# Control_Board.net
KiCad netlist of a schematic drawn in Altium Designer
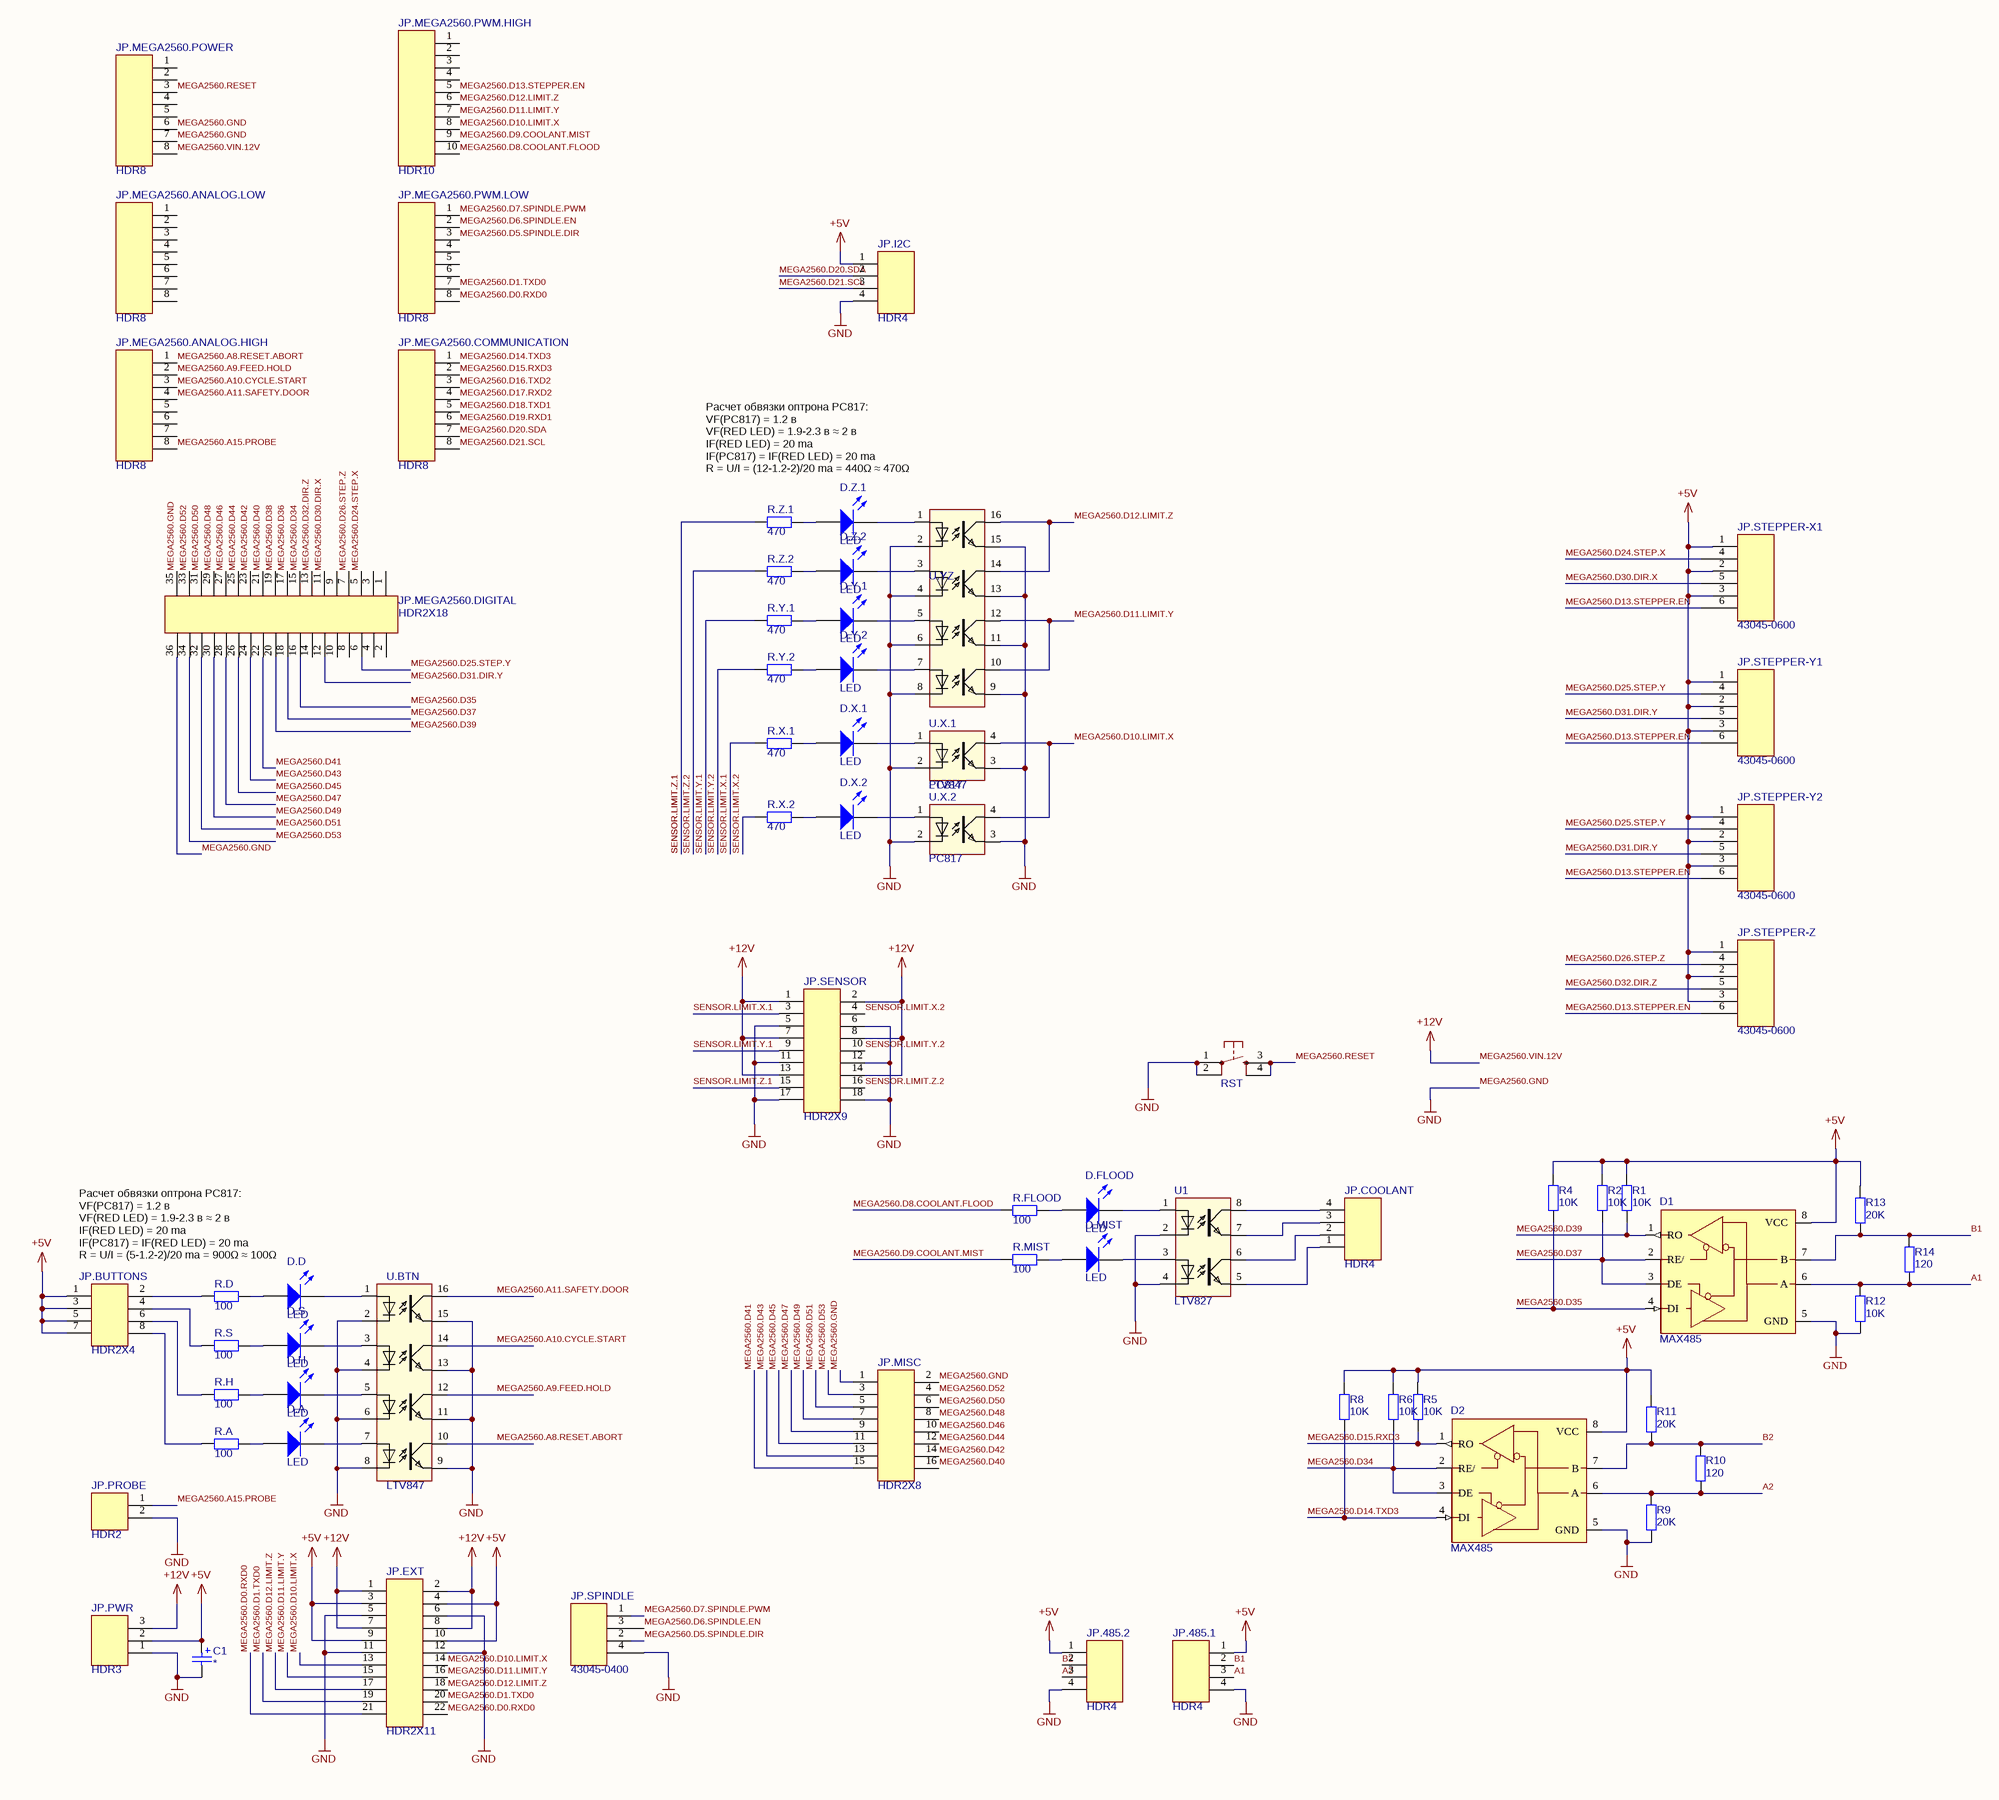
[diagram p0: Control.Board.SchDoc]

(export (version "E")
  (design (tool "Eeschema 10.0.6"))
  (components
    (comp (ref "C1")
      (value "*")
      (footprint "E3,5-8")
      (description "Polarized Capacitor (Radial)")
      (fields (field (name "PUBLISHER") "Altium Limited"))
      (libsource (lib "Net173") (part "CAP.POL"))
    )
    (comp (ref "D.A")
      (value "LED")
      (footprint "1206-SMD-LED")
      (fields (field (name "PUBLISHER") "Altium Limited"))
      (libsource (lib "Net173") (part "LED"))
    )
    (comp (ref "D.D")
      (value "LED")
      (footprint "1206-SMD-LED")
      (fields (field (name "PUBLISHER") "Altium Limited"))
      (libsource (lib "Net173") (part "LED"))
    )
    (comp (ref "D.FLOOD")
      (value "LED")
      (footprint "1206-SMD-LED")
      (fields (field (name "PUBLISHER") "Altium Limited"))
      (libsource (lib "Net173") (part "LED"))
    )
    (comp (ref "D.H")
      (value "LED")
      (footprint "1206-SMD-LED")
      (fields (field (name "PUBLISHER") "Altium Limited"))
      (libsource (lib "Net173") (part "LED"))
    )
    (comp (ref "D.MIST")
      (value "LED")
      (footprint "1206-SMD-LED")
      (fields (field (name "PUBLISHER") "Altium Limited"))
      (libsource (lib "Net173") (part "LED"))
    )
    (comp (ref "D.S")
      (value "LED")
      (footprint "1206-SMD-LED")
      (fields (field (name "PUBLISHER") "Altium Limited"))
      (libsource (lib "Net173") (part "LED"))
    )
    (comp (ref "D.X.1")
      (value "LED")
      (footprint "1206-SMD-LED")
      (fields (field (name "PUBLISHER") "Altium Limited"))
      (libsource (lib "Net173") (part "LED"))
    )
    (comp (ref "D.X.2")
      (value "LED")
      (footprint "1206-SMD-LED")
      (fields (field (name "PUBLISHER") "Altium Limited"))
      (libsource (lib "Net173") (part "LED"))
    )
    (comp (ref "D.Y.1")
      (value "LED")
      (footprint "1206-SMD-LED")
      (fields (field (name "PUBLISHER") "Altium Limited"))
      (libsource (lib "Net173") (part "LED"))
    )
    (comp (ref "D.Y.2")
      (value "LED")
      (footprint "1206-SMD-LED")
      (fields (field (name "PUBLISHER") "Altium Limited"))
      (libsource (lib "Net173") (part "LED"))
    )
    (comp (ref "D.Z.1")
      (value "LED")
      (footprint "1206-SMD-LED")
      (fields (field (name "PUBLISHER") "Altium Limited"))
      (libsource (lib "Net173") (part "LED"))
    )
    (comp (ref "D.Z.2")
      (value "LED")
      (footprint "1206-SMD-LED")
      (fields (field (name "PUBLISHER") "Altium Limited"))
      (libsource (lib "Net173") (part "LED"))
    )
    (comp (ref "D1") (value "MAX485") (footprint "DIP8") (libsource (lib "Net173") (part "MAX485")))
    (comp (ref "D2") (value "MAX485") (footprint "DIP8") (libsource (lib "Net173") (part "MAX485")))
    (comp (ref "JP.485.1") (value "HDR4") (footprint "HDR1X4") (libsource (lib "") (part "HDR4_1")))
    (comp (ref "JP.485.2") (value "HDR4") (footprint "HDR1X4") (libsource (lib "Net173") (part "HDR4")))
    (comp (ref "JP.BUTTONS") (value "HDR2X4") (footprint "HDR2X4") (libsource (lib "Net173") (part "HDR2X4")))
    (comp (ref "JP.COOLANT") (value "HDR4") (footprint "HDR1X4H") (libsource (lib "") (part "HDR4_2")))
    (comp (ref "JP.EXT") (value "HDR2X11") (footprint "HDR2X11") (libsource (lib "Net173") (part "HDR2X11")))
    (comp (ref "JP.I2C") (value "HDR4") (footprint "HDR1X4") (libsource (lib "Net173") (part "HDR4")))
    (comp (ref "JP.MEGA2560.ANALOG.HIGH")
      (value "HDR8")
      (footprint "HDR8-BOTTOM")
      (libsource (lib "Net173") (part "HDR8"))
    )
    (comp (ref "JP.MEGA2560.ANALOG.LOW")
      (value "HDR8")
      (footprint "HDR8-BOTTOM")
      (libsource (lib "Net173") (part "HDR8"))
    )
    (comp (ref "JP.MEGA2560.COMMUNICATION")
      (value "HDR8")
      (footprint "HDR8-BOTTOM")
      (libsource (lib "Net173") (part "HDR8"))
    )
    (comp (ref "JP.MEGA2560.DIGITAL")
      (value "HDR2X18")
      (footprint "HDR2X18-BOTTOM")
      (libsource (lib "Net173") (part "HDR2X18"))
    )
    (comp (ref "JP.MEGA2560.POWER")
      (value "HDR8")
      (footprint "HDR8-BOTTOM")
      (libsource (lib "Net173") (part "HDR8"))
    )
    (comp (ref "JP.MEGA2560.PWM.HIGH")
      (value "HDR10")
      (footprint "HDR10-BOTTOM")
      (libsource (lib "Net173") (part "HDR10"))
    )
    (comp (ref "JP.MEGA2560.PWM.LOW")
      (value "HDR8")
      (footprint "HDR8-BOTTOM")
      (libsource (lib "Net173") (part "HDR8"))
    )
    (comp (ref "JP.MISC") (value "HDR2X8") (footprint "HDR2X8") (libsource (lib "Net173") (part "HDR2X8")))
    (comp (ref "JP.PROBE") (value "HDR2") (footprint "HDR1X2") (libsource (lib "Net173") (part "HDR2")))
    (comp (ref "JP.PWR") (value "HDR3") (footprint "HDR1X3H") (libsource (lib "Net173") (part "HDR3")))
    (comp (ref "JP.SENSOR") (value "HDR2X9") (footprint "HDR2X9") (libsource (lib "Net173") (part "HDR2X9")))
    (comp (ref "JP.SPINDLE")
      (value "43045-0400")
      (footprint "43045-0400")
      (libsource (lib "Net173") (part "43045-0400"))
    )
    (comp (ref "JP.STEPPER-X1")
      (value "43045-0600")
      (footprint "43045-0600")
      (libsource (lib "Net173") (part "43045-0600"))
    )
    (comp (ref "JP.STEPPER-Y1")
      (value "43045-0600")
      (footprint "43045-0600")
      (libsource (lib "Net173") (part "43045-0600"))
    )
    (comp (ref "JP.STEPPER-Y2")
      (value "43045-0600")
      (footprint "43045-0600")
      (libsource (lib "Net173") (part "43045-0600"))
    )
    (comp (ref "JP.STEPPER-Z")
      (value "43045-0600")
      (footprint "43045-0600")
      (libsource (lib "Net173") (part "43045-0600"))
    )
    (comp (ref "R.A") (value "100") (footprint "1206-SMD-RES") (libsource (lib "Net173") (part "RES")))
    (comp (ref "R.D") (value "100") (footprint "1206-SMD-RES") (libsource (lib "Net173") (part "RES")))
    (comp (ref "R.FLOOD") (value "100") (footprint "1206-SMD-RES") (libsource (lib "Net173") (part "RES")))
    (comp (ref "R.H") (value "100") (footprint "1206-SMD-RES") (libsource (lib "Net173") (part "RES")))
    (comp (ref "R.MIST") (value "100") (footprint "1206-SMD-RES") (libsource (lib "Net173") (part "RES")))
    (comp (ref "R.S") (value "100") (footprint "1206-SMD-RES") (libsource (lib "Net173") (part "RES")))
    (comp (ref "R.X.1") (value "470") (footprint "1206-SMD-RES") (libsource (lib "Net173") (part "RES")))
    (comp (ref "R.X.2") (value "470") (footprint "1206-SMD-RES") (libsource (lib "Net173") (part "RES")))
    (comp (ref "R.Y.1") (value "470") (footprint "1206-SMD-RES") (libsource (lib "Net173") (part "RES")))
    (comp (ref "R.Y.2") (value "470") (footprint "1206-SMD-RES") (libsource (lib "Net173") (part "RES")))
    (comp (ref "R.Z.1") (value "470") (footprint "1206-SMD-RES") (libsource (lib "Net173") (part "RES")))
    (comp (ref "R.Z.2") (value "470") (footprint "1206-SMD-RES") (libsource (lib "Net173") (part "RES")))
    (comp (ref "R1") (value "10K") (footprint "1206-SMD-RES") (libsource (lib "") (part "RES_1")))
    (comp (ref "R2") (value "10K") (footprint "1206-SMD-RES") (libsource (lib "") (part "RES_1")))
    (comp (ref "R4") (value "10K") (footprint "1206-SMD-RES") (libsource (lib "") (part "RES_1")))
    (comp (ref "R5") (value "10K") (footprint "1206-SMD-RES") (libsource (lib "") (part "RES_1")))
    (comp (ref "R6") (value "10K") (footprint "1206-SMD-RES") (libsource (lib "") (part "RES_1")))
    (comp (ref "R8") (value "10K") (footprint "1206-SMD-RES") (libsource (lib "") (part "RES_1")))
    (comp (ref "R9") (value "20K") (footprint "1206-SMD-RES") (libsource (lib "") (part "RES_1")))
    (comp (ref "R10") (value "120") (footprint "1206-SMD-RES") (libsource (lib "") (part "RES_1")))
    (comp (ref "R11") (value "20K") (footprint "1206-SMD-RES") (libsource (lib "") (part "RES_1")))
    (comp (ref "R12") (value "10K") (footprint "1206-SMD-RES") (libsource (lib "") (part "RES_1")))
    (comp (ref "R13") (value "20K") (footprint "1206-SMD-RES") (libsource (lib "") (part "RES_1")))
    (comp (ref "R14") (value "120") (footprint "1206-SMD-RES") (libsource (lib "") (part "RES_1")))
    (comp (ref "RST")
      (value "OMRON SWITCH")
      (footprint "B3F-10XX")
      (fields (field (name "MPN") "B3F-1000"))
      (libsource (lib "Net173") (part "B3F-10-XX"))
    )
    (comp (ref "U.BTN") (value "LTV847") (footprint "DIP16") (libsource (lib "Net173") (part "LTV847")))
    (comp (ref "U.X.1") (value "PC817") (footprint "DIP4") (libsource (lib "Net173") (part "PC817")))
    (comp (ref "U.X.2") (value "PC817") (footprint "DIP4") (libsource (lib "Net173") (part "PC817")))
    (comp (ref "U.YZ") (value "LTV847") (footprint "DIP16") (libsource (lib "Net173") (part "LTV847")))
    (comp (ref "U1") (value "LTV827") (footprint "DIP8") (libsource (lib "Net173") (part "LTV827")))
  )
  (nets
    (net (code "1") (name "+5V") (class "Default")
      (node (ref "C1") (pin "+") (pinfunction "1_+") (pintype "passive"))
      (node (ref "D1") (pin "8") (pinfunction "VCC_8") (pintype "power_in"))
      (node (ref "D2") (pin "8") (pinfunction "VCC_8") (pintype "power_in"))
      (node (ref "JP.485.1") (pin "1") (pinfunction "1_1") (pintype "passive"))
      (node (ref "JP.485.2") (pin "1") (pinfunction "1_1") (pintype "passive"))
      (node (ref "JP.BUTTONS") (pin "1") (pinfunction "1_1") (pintype "passive"))
      (node (ref "JP.BUTTONS") (pin "3") (pinfunction "3_3") (pintype "passive"))
      (node (ref "JP.BUTTONS") (pin "5") (pinfunction "5_5") (pintype "passive"))
      (node (ref "JP.BUTTONS") (pin "7") (pinfunction "7_7") (pintype "passive"))
      (node (ref "JP.EXT") (pin "10") (pinfunction "10_10") (pintype "passive"))
      (node (ref "JP.EXT") (pin "3") (pinfunction "3_3") (pintype "passive"))
      (node (ref "JP.EXT") (pin "4") (pinfunction "4_4") (pintype "passive"))
      (node (ref "JP.EXT") (pin "9") (pinfunction "9_9") (pintype "passive"))
      (node (ref "JP.I2C") (pin "1") (pinfunction "1_1") (pintype "passive"))
      (node (ref "JP.PWR") (pin "2") (pinfunction "2_2") (pintype "passive"))
      (node (ref "JP.STEPPER-X1") (pin "1") (pinfunction "1_1") (pintype "passive"))
      (node (ref "JP.STEPPER-X1") (pin "2") (pinfunction "2_2") (pintype "passive"))
      (node (ref "JP.STEPPER-X1") (pin "3") (pinfunction "3_3") (pintype "passive"))
      (node (ref "JP.STEPPER-Y1") (pin "1") (pinfunction "1_1") (pintype "passive"))
      (node (ref "JP.STEPPER-Y1") (pin "2") (pinfunction "2_2") (pintype "passive"))
      (node (ref "JP.STEPPER-Y1") (pin "3") (pinfunction "3_3") (pintype "passive"))
      (node (ref "JP.STEPPER-Y2") (pin "1") (pinfunction "1_1") (pintype "passive"))
      (node (ref "JP.STEPPER-Y2") (pin "2") (pinfunction "2_2") (pintype "passive"))
      (node (ref "JP.STEPPER-Y2") (pin "3") (pinfunction "3_3") (pintype "passive"))
      (node (ref "JP.STEPPER-Z") (pin "1") (pinfunction "1_1") (pintype "passive"))
      (node (ref "JP.STEPPER-Z") (pin "2") (pinfunction "2_2") (pintype "passive"))
      (node (ref "JP.STEPPER-Z") (pin "3") (pinfunction "3_3") (pintype "passive"))
      (node (ref "R1") (pin "2") (pinfunction "2_2") (pintype "passive"))
      (node (ref "R11") (pin "2") (pinfunction "2_2") (pintype "passive"))
      (node (ref "R13") (pin "2") (pinfunction "2_2") (pintype "passive"))
      (node (ref "R2") (pin "2") (pinfunction "2_2") (pintype "passive"))
      (node (ref "R4") (pin "2") (pinfunction "2_2") (pintype "passive"))
      (node (ref "R5") (pin "2") (pinfunction "2_2") (pintype "passive"))
      (node (ref "R6") (pin "2") (pinfunction "2_2") (pintype "passive"))
      (node (ref "R8") (pin "2") (pinfunction "2_2") (pintype "passive"))
    )
    (net (code "2") (name "+12V") (class "Default")
      (node (ref "JP.EXT") (pin "1") (pinfunction "1_1") (pintype "passive"))
      (node (ref "JP.EXT") (pin "2") (pinfunction "2_2") (pintype "passive"))
      (node (ref "JP.EXT") (pin "7") (pinfunction "7_7") (pintype "passive"))
      (node (ref "JP.EXT") (pin "8") (pinfunction "8_8") (pintype "passive"))
      (node (ref "JP.MEGA2560.POWER") (pin "8") (pinfunction "8_8") (pintype "passive"))
      (node (ref "JP.PWR") (pin "3") (pinfunction "3_3") (pintype "passive"))
      (node (ref "JP.SENSOR") (pin "1") (pinfunction "1_1") (pintype "passive"))
      (node (ref "JP.SENSOR") (pin "13") (pinfunction "13_13") (pintype "passive"))
      (node (ref "JP.SENSOR") (pin "14") (pinfunction "14_14") (pintype "passive"))
      (node (ref "JP.SENSOR") (pin "2") (pinfunction "2_2") (pintype "passive"))
      (node (ref "JP.SENSOR") (pin "7") (pinfunction "7_7") (pintype "passive"))
      (node (ref "JP.SENSOR") (pin "8") (pinfunction "8_8") (pintype "passive"))
    )
    (net (code "3") (name "/A1") (class "Default")
      (node (ref "D1") (pin "6") (pinfunction "A_6") (pintype "passive"))
      (node (ref "JP.485.1") (pin "3") (pinfunction "3_3") (pintype "passive"))
      (node (ref "R12") (pin "2") (pinfunction "2_2") (pintype "passive"))
      (node (ref "R14") (pin "1") (pinfunction "1_1") (pintype "passive"))
    )
    (net (code "4") (name "/A2") (class "Default")
      (node (ref "D2") (pin "6") (pinfunction "A_6") (pintype "passive"))
      (node (ref "JP.485.2") (pin "3") (pinfunction "3_3") (pintype "passive"))
      (node (ref "R10") (pin "1") (pinfunction "1_1") (pintype "passive"))
      (node (ref "R9") (pin "2") (pinfunction "2_2") (pintype "passive"))
    )
    (net (code "5") (name "/B1") (class "Default")
      (node (ref "D1") (pin "7") (pinfunction "B_7") (pintype "passive"))
      (node (ref "JP.485.1") (pin "2") (pinfunction "2_2") (pintype "passive"))
      (node (ref "R13") (pin "1") (pinfunction "1_1") (pintype "passive"))
      (node (ref "R14") (pin "2") (pinfunction "2_2") (pintype "passive"))
    )
    (net (code "6") (name "/B2") (class "Default")
      (node (ref "D2") (pin "7") (pinfunction "B_7") (pintype "passive"))
      (node (ref "JP.485.2") (pin "2") (pinfunction "2_2") (pintype "passive"))
      (node (ref "R10") (pin "2") (pinfunction "2_2") (pintype "passive"))
      (node (ref "R11") (pin "1") (pinfunction "1_1") (pintype "passive"))
    )
    (net (code "7") (name "/MEGA2560.A8.RESET.ABORT") (class "Default")
      (node (ref "JP.MEGA2560.ANALOG.HIGH") (pin "1") (pinfunction "1_1") (pintype "passive"))
      (node (ref "U.BTN") (pin "10") (pinfunction "10_10") (pintype "passive"))
    )
    (net (code "8") (name "/MEGA2560.A9.FEED.HOLD") (class "Default")
      (node (ref "JP.MEGA2560.ANALOG.HIGH") (pin "2") (pinfunction "2_2") (pintype "passive"))
      (node (ref "U.BTN") (pin "12") (pinfunction "12_12") (pintype "passive"))
    )
    (net (code "9") (name "/MEGA2560.A10.CYCLE.START") (class "Default")
      (node (ref "JP.MEGA2560.ANALOG.HIGH") (pin "3") (pinfunction "3_3") (pintype "passive"))
      (node (ref "U.BTN") (pin "14") (pinfunction "14_14") (pintype "passive"))
    )
    (net (code "10") (name "/MEGA2560.A11.SAFETY.DOOR") (class "Default")
      (node (ref "JP.MEGA2560.ANALOG.HIGH") (pin "4") (pinfunction "4_4") (pintype "passive"))
      (node (ref "U.BTN") (pin "16") (pinfunction "16_16") (pintype "passive"))
    )
    (net (code "11") (name "/MEGA2560.A15.PROBE") (class "Default")
      (node (ref "JP.MEGA2560.ANALOG.HIGH") (pin "8") (pinfunction "8_8") (pintype "passive"))
      (node (ref "JP.PROBE") (pin "1") (pinfunction "1_1") (pintype "passive"))
    )
    (net (code "12") (name "/MEGA2560.D0.RXD0") (class "Default")
      (node (ref "JP.EXT") (pin "21") (pinfunction "21_21") (pintype "passive"))
      (node (ref "JP.EXT") (pin "22") (pinfunction "22_22") (pintype "passive"))
      (node (ref "JP.MEGA2560.PWM.LOW") (pin "8") (pinfunction "8_8") (pintype "passive"))
    )
    (net (code "13") (name "/MEGA2560.D1.TXD0") (class "Default")
      (node (ref "JP.EXT") (pin "19") (pinfunction "19_19") (pintype "passive"))
      (node (ref "JP.EXT") (pin "20") (pinfunction "20_20") (pintype "passive"))
      (node (ref "JP.MEGA2560.PWM.LOW") (pin "7") (pinfunction "7_7") (pintype "passive"))
    )
    (net (code "14") (name "/MEGA2560.D5.SPINDLE.DIR") (class "Default")
      (node (ref "JP.MEGA2560.PWM.LOW") (pin "3") (pinfunction "3_3") (pintype "passive"))
      (node (ref "JP.SPINDLE") (pin "2") (pinfunction "2_2") (pintype "passive"))
    )
    (net (code "15") (name "/MEGA2560.D6.SPINDLE.EN") (class "Default")
      (node (ref "JP.MEGA2560.PWM.LOW") (pin "2") (pinfunction "2_2") (pintype "passive"))
      (node (ref "JP.SPINDLE") (pin "3") (pinfunction "3_3") (pintype "passive"))
    )
    (net (code "16") (name "/MEGA2560.D7.SPINDLE.PWM") (class "Default")
      (node (ref "JP.MEGA2560.PWM.LOW") (pin "1") (pinfunction "1_1") (pintype "passive"))
      (node (ref "JP.SPINDLE") (pin "1") (pinfunction "1_1") (pintype "passive"))
    )
    (net (code "17") (name "/MEGA2560.D8.COOLANT.FLOOD") (class "Default")
      (node (ref "JP.MEGA2560.PWM.HIGH") (pin "10") (pinfunction "10_10") (pintype "passive"))
      (node (ref "R.FLOOD") (pin "1") (pinfunction "1_1") (pintype "passive"))
    )
    (net (code "18") (name "/MEGA2560.D9.COOLANT.MIST") (class "Default")
      (node (ref "JP.MEGA2560.PWM.HIGH") (pin "9") (pinfunction "9_9") (pintype "passive"))
      (node (ref "R.MIST") (pin "1") (pinfunction "1_1") (pintype "passive"))
    )
    (net (code "19") (name "/MEGA2560.D10.LIMIT.X") (class "Default")
      (node (ref "JP.EXT") (pin "13") (pinfunction "13_13") (pintype "passive"))
      (node (ref "JP.EXT") (pin "14") (pinfunction "14_14") (pintype "passive"))
      (node (ref "JP.MEGA2560.PWM.HIGH") (pin "8") (pinfunction "8_8") (pintype "passive"))
      (node (ref "U.X.1") (pin "4") (pintype "passive"))
      (node (ref "U.X.2") (pin "4") (pintype "passive"))
    )
    (net (code "20") (name "/MEGA2560.D11.LIMIT.Y") (class "Default")
      (node (ref "JP.EXT") (pin "15") (pinfunction "15_15") (pintype "passive"))
      (node (ref "JP.EXT") (pin "16") (pinfunction "16_16") (pintype "passive"))
      (node (ref "JP.MEGA2560.PWM.HIGH") (pin "7") (pinfunction "7_7") (pintype "passive"))
      (node (ref "U.YZ") (pin "10") (pinfunction "10_10") (pintype "passive"))
      (node (ref "U.YZ") (pin "12") (pinfunction "12_12") (pintype "passive"))
    )
    (net (code "21") (name "/MEGA2560.D12.LIMIT.Z") (class "Default")
      (node (ref "JP.EXT") (pin "17") (pinfunction "17_17") (pintype "passive"))
      (node (ref "JP.EXT") (pin "18") (pinfunction "18_18") (pintype "passive"))
      (node (ref "JP.MEGA2560.PWM.HIGH") (pin "6") (pinfunction "6_6") (pintype "passive"))
      (node (ref "U.YZ") (pin "14") (pinfunction "14_14") (pintype "passive"))
      (node (ref "U.YZ") (pin "16") (pinfunction "16_16") (pintype "passive"))
    )
    (net (code "22") (name "/MEGA2560.D13.STEPPER.EN") (class "Default")
      (node (ref "JP.MEGA2560.PWM.HIGH") (pin "5") (pinfunction "5_5") (pintype "passive"))
      (node (ref "JP.STEPPER-X1") (pin "6") (pinfunction "6_6") (pintype "passive"))
      (node (ref "JP.STEPPER-Y1") (pin "6") (pinfunction "6_6") (pintype "passive"))
      (node (ref "JP.STEPPER-Y2") (pin "6") (pinfunction "6_6") (pintype "passive"))
      (node (ref "JP.STEPPER-Z") (pin "6") (pinfunction "6_6") (pintype "passive"))
    )
    (net (code "23") (name "/MEGA2560.D14.TXD3") (class "Default")
      (node (ref "D2") (pin "4") (pinfunction "DI_4") (pintype "input"))
      (node (ref "JP.MEGA2560.COMMUNICATION") (pin "1") (pinfunction "1_1") (pintype "passive"))
      (node (ref "R8") (pin "1") (pinfunction "1_1") (pintype "passive"))
    )
    (net (code "24") (name "/MEGA2560.D15.RXD3") (class "Default")
      (node (ref "D2") (pin "1") (pinfunction "RO_1") (pintype "output"))
      (node (ref "JP.MEGA2560.COMMUNICATION") (pin "2") (pinfunction "2_2") (pintype "passive"))
      (node (ref "R5") (pin "1") (pinfunction "1_1") (pintype "passive"))
    )
    (net (code "25") (name "/MEGA2560.D16.TXD2") (class "Default")
      (node (ref "JP.MEGA2560.COMMUNICATION") (pin "3") (pinfunction "3_3") (pintype "passive"))
    )
    (net (code "26") (name "/MEGA2560.D17.RXD2") (class "Default")
      (node (ref "JP.MEGA2560.COMMUNICATION") (pin "4") (pinfunction "4_4") (pintype "passive"))
    )
    (net (code "27") (name "/MEGA2560.D18.TXD1") (class "Default")
      (node (ref "JP.MEGA2560.COMMUNICATION") (pin "5") (pinfunction "5_5") (pintype "passive"))
    )
    (net (code "28") (name "/MEGA2560.D19.RXD1") (class "Default")
      (node (ref "JP.MEGA2560.COMMUNICATION") (pin "6") (pinfunction "6_6") (pintype "passive"))
    )
    (net (code "29") (name "/MEGA2560.D20.SDA") (class "Default")
      (node (ref "JP.I2C") (pin "2") (pinfunction "2_2") (pintype "passive"))
      (node (ref "JP.MEGA2560.COMMUNICATION") (pin "7") (pinfunction "7_7") (pintype "passive"))
    )
    (net (code "30") (name "/MEGA2560.D21.SCL") (class "Default")
      (node (ref "JP.I2C") (pin "3") (pinfunction "3_3") (pintype "passive"))
      (node (ref "JP.MEGA2560.COMMUNICATION") (pin "8") (pinfunction "8_8") (pintype "passive"))
    )
    (net (code "31") (name "/MEGA2560.D24.STEP.X") (class "Default")
      (node (ref "JP.MEGA2560.DIGITAL") (pin "5") (pinfunction "5_5") (pintype "passive"))
      (node (ref "JP.STEPPER-X1") (pin "4") (pinfunction "4_4") (pintype "passive"))
    )
    (net (code "32") (name "/MEGA2560.D25.STEP.Y") (class "Default")
      (node (ref "JP.MEGA2560.DIGITAL") (pin "6") (pinfunction "6_6") (pintype "passive"))
      (node (ref "JP.STEPPER-Y1") (pin "4") (pinfunction "4_4") (pintype "passive"))
      (node (ref "JP.STEPPER-Y2") (pin "4") (pinfunction "4_4") (pintype "passive"))
    )
    (net (code "33") (name "/MEGA2560.D26.STEP.Z") (class "Default")
      (node (ref "JP.MEGA2560.DIGITAL") (pin "7") (pinfunction "7_7") (pintype "passive"))
      (node (ref "JP.STEPPER-Z") (pin "4") (pinfunction "4_4") (pintype "passive"))
    )
    (net (code "34") (name "/MEGA2560.D30.DIR.X") (class "Default")
      (node (ref "JP.MEGA2560.DIGITAL") (pin "11") (pinfunction "11_11") (pintype "passive"))
      (node (ref "JP.STEPPER-X1") (pin "5") (pinfunction "5_5") (pintype "passive"))
    )
    (net (code "35") (name "/MEGA2560.D31.DIR.Y") (class "Default")
      (node (ref "JP.MEGA2560.DIGITAL") (pin "12") (pinfunction "12_12") (pintype "passive"))
      (node (ref "JP.STEPPER-Y1") (pin "5") (pinfunction "5_5") (pintype "passive"))
      (node (ref "JP.STEPPER-Y2") (pin "5") (pinfunction "5_5") (pintype "passive"))
    )
    (net (code "36") (name "/MEGA2560.D32.DIR.Z") (class "Default")
      (node (ref "JP.MEGA2560.DIGITAL") (pin "13") (pinfunction "13_13") (pintype "passive"))
      (node (ref "JP.STEPPER-Z") (pin "5") (pinfunction "5_5") (pintype "passive"))
    )
    (net (code "37") (name "/MEGA2560.D34") (class "Default")
      (node (ref "D2") (pin "2") (pinfunction "RE/_2") (pintype "passive"))
      (node (ref "D2") (pin "3") (pinfunction "DE_3") (pintype "passive"))
      (node (ref "JP.MEGA2560.DIGITAL") (pin "15") (pinfunction "15_15") (pintype "passive"))
      (node (ref "R6") (pin "1") (pinfunction "1_1") (pintype "passive"))
    )
    (net (code "38") (name "/MEGA2560.D35") (class "Default")
      (node (ref "D1") (pin "4") (pinfunction "DI_4") (pintype "input"))
      (node (ref "JP.MEGA2560.DIGITAL") (pin "16") (pinfunction "16_16") (pintype "passive"))
      (node (ref "R4") (pin "1") (pinfunction "1_1") (pintype "passive"))
    )
    (net (code "39") (name "/MEGA2560.D36") (class "Default")
      (node (ref "JP.MEGA2560.DIGITAL") (pin "17") (pinfunction "17_17") (pintype "passive"))
    )
    (net (code "40") (name "/MEGA2560.D37") (class "Default")
      (node (ref "D1") (pin "2") (pinfunction "RE/_2") (pintype "passive"))
      (node (ref "D1") (pin "3") (pinfunction "DE_3") (pintype "passive"))
      (node (ref "JP.MEGA2560.DIGITAL") (pin "18") (pinfunction "18_18") (pintype "passive"))
      (node (ref "R2") (pin "1") (pinfunction "1_1") (pintype "passive"))
    )
    (net (code "41") (name "/MEGA2560.D38") (class "Default")
      (node (ref "JP.MEGA2560.DIGITAL") (pin "19") (pinfunction "19_19") (pintype "passive"))
    )
    (net (code "42") (name "/MEGA2560.D39") (class "Default")
      (node (ref "D1") (pin "1") (pinfunction "RO_1") (pintype "output"))
      (node (ref "JP.MEGA2560.DIGITAL") (pin "20") (pinfunction "20_20") (pintype "passive"))
      (node (ref "R1") (pin "1") (pinfunction "1_1") (pintype "passive"))
    )
    (net (code "43") (name "/MEGA2560.D40") (class "Default")
      (node (ref "JP.MEGA2560.DIGITAL") (pin "21") (pinfunction "21_21") (pintype "passive"))
      (node (ref "JP.MISC") (pin "16") (pinfunction "16_16") (pintype "passive"))
    )
    (net (code "44") (name "/MEGA2560.D41") (class "Default")
      (node (ref "JP.MEGA2560.DIGITAL") (pin "22") (pinfunction "22_22") (pintype "passive"))
      (node (ref "JP.MISC") (pin "15") (pinfunction "15_15") (pintype "passive"))
    )
    (net (code "45") (name "/MEGA2560.D42") (class "Default")
      (node (ref "JP.MEGA2560.DIGITAL") (pin "23") (pinfunction "23_23") (pintype "passive"))
      (node (ref "JP.MISC") (pin "14") (pinfunction "14_14") (pintype "passive"))
    )
    (net (code "46") (name "/MEGA2560.D43") (class "Default")
      (node (ref "JP.MEGA2560.DIGITAL") (pin "24") (pinfunction "24_24") (pintype "passive"))
      (node (ref "JP.MISC") (pin "13") (pinfunction "13_13") (pintype "passive"))
    )
    (net (code "47") (name "/MEGA2560.D44") (class "Default")
      (node (ref "JP.MEGA2560.DIGITAL") (pin "25") (pinfunction "25_25") (pintype "passive"))
      (node (ref "JP.MISC") (pin "12") (pinfunction "12_12") (pintype "passive"))
    )
    (net (code "48") (name "/MEGA2560.D45") (class "Default")
      (node (ref "JP.MEGA2560.DIGITAL") (pin "26") (pinfunction "26_26") (pintype "passive"))
      (node (ref "JP.MISC") (pin "11") (pinfunction "11_11") (pintype "passive"))
    )
    (net (code "49") (name "/MEGA2560.D46") (class "Default")
      (node (ref "JP.MEGA2560.DIGITAL") (pin "27") (pinfunction "27_27") (pintype "passive"))
      (node (ref "JP.MISC") (pin "10") (pinfunction "10_10") (pintype "passive"))
    )
    (net (code "50") (name "/MEGA2560.D47") (class "Default")
      (node (ref "JP.MEGA2560.DIGITAL") (pin "28") (pinfunction "28_28") (pintype "passive"))
      (node (ref "JP.MISC") (pin "9") (pinfunction "9_9") (pintype "passive"))
    )
    (net (code "51") (name "/MEGA2560.D48") (class "Default")
      (node (ref "JP.MEGA2560.DIGITAL") (pin "29") (pinfunction "29_29") (pintype "passive"))
      (node (ref "JP.MISC") (pin "8") (pinfunction "8_8") (pintype "passive"))
    )
    (net (code "52") (name "/MEGA2560.D49") (class "Default")
      (node (ref "JP.MEGA2560.DIGITAL") (pin "30") (pinfunction "30_30") (pintype "passive"))
      (node (ref "JP.MISC") (pin "7") (pinfunction "7_7") (pintype "passive"))
    )
    (net (code "53") (name "/MEGA2560.D50") (class "Default")
      (node (ref "JP.MEGA2560.DIGITAL") (pin "31") (pinfunction "31_31") (pintype "passive"))
      (node (ref "JP.MISC") (pin "6") (pinfunction "6_6") (pintype "passive"))
    )
    (net (code "54") (name "/MEGA2560.D51") (class "Default")
      (node (ref "JP.MEGA2560.DIGITAL") (pin "32") (pinfunction "32_32") (pintype "passive"))
      (node (ref "JP.MISC") (pin "5") (pinfunction "5_5") (pintype "passive"))
    )
    (net (code "55") (name "/MEGA2560.D52") (class "Default")
      (node (ref "JP.MEGA2560.DIGITAL") (pin "33") (pinfunction "33_33") (pintype "passive"))
      (node (ref "JP.MISC") (pin "4") (pinfunction "4_4") (pintype "passive"))
    )
    (net (code "56") (name "/MEGA2560.D53") (class "Default")
      (node (ref "JP.MEGA2560.DIGITAL") (pin "34") (pinfunction "34_34") (pintype "passive"))
      (node (ref "JP.MISC") (pin "3") (pinfunction "3_3") (pintype "passive"))
    )
    (net (code "57") (name "/MEGA2560.RESET") (class "Default")
      (node (ref "JP.MEGA2560.POWER") (pin "3") (pinfunction "3_3") (pintype "passive"))
      (node (ref "RST") (pin "3") (pinfunction "P_3") (pintype "passive"))
      (node (ref "RST") (pin "4") (pinfunction "P1_4") (pintype "passive"))
    )
    (net (code "58") (name "/SENSOR.LIMIT.X.1") (class "Default")
      (node (ref "JP.SENSOR") (pin "3") (pinfunction "3_3") (pintype "passive"))
      (node (ref "R.X.1") (pin "1") (pinfunction "1_1") (pintype "passive"))
    )
    (net (code "59") (name "/SENSOR.LIMIT.X.2") (class "Default")
      (node (ref "JP.SENSOR") (pin "4") (pinfunction "4_4") (pintype "passive"))
      (node (ref "R.X.2") (pin "1") (pinfunction "1_1") (pintype "passive"))
    )
    (net (code "60") (name "/SENSOR.LIMIT.Y.1") (class "Default")
      (node (ref "JP.SENSOR") (pin "9") (pinfunction "9_9") (pintype "passive"))
      (node (ref "R.Y.1") (pin "1") (pinfunction "1_1") (pintype "passive"))
    )
    (net (code "61") (name "/SENSOR.LIMIT.Y.2") (class "Default")
      (node (ref "JP.SENSOR") (pin "10") (pinfunction "10_10") (pintype "passive"))
      (node (ref "R.Y.2") (pin "1") (pinfunction "1_1") (pintype "passive"))
    )
    (net (code "62") (name "/SENSOR.LIMIT.Z.1") (class "Default")
      (node (ref "JP.SENSOR") (pin "15") (pinfunction "15_15") (pintype "passive"))
      (node (ref "R.Z.1") (pin "1") (pinfunction "1_1") (pintype "passive"))
    )
    (net (code "63") (name "/SENSOR.LIMIT.Z.2") (class "Default")
      (node (ref "JP.SENSOR") (pin "16") (pinfunction "16_16") (pintype "passive"))
      (node (ref "R.Z.2") (pin "1") (pinfunction "1_1") (pintype "passive"))
    )
    (net (code "64") (name "GND") (class "Default")
      (node (ref "C1") (pin "-") (pinfunction "2_-") (pintype "passive"))
      (node (ref "D1") (pin "5") (pinfunction "GND_5") (pintype "power_in"))
      (node (ref "D2") (pin "5") (pinfunction "GND_5") (pintype "power_in"))
      (node (ref "JP.485.1") (pin "4") (pinfunction "4_4") (pintype "passive"))
      (node (ref "JP.485.2") (pin "4") (pinfunction "4_4") (pintype "passive"))
      (node (ref "JP.EXT") (pin "11") (pinfunction "11_11") (pintype "passive"))
      (node (ref "JP.EXT") (pin "12") (pinfunction "12_12") (pintype "passive"))
      (node (ref "JP.EXT") (pin "5") (pinfunction "5_5") (pintype "passive"))
      (node (ref "JP.EXT") (pin "6") (pinfunction "6_6") (pintype "passive"))
      (node (ref "JP.I2C") (pin "4") (pinfunction "4_4") (pintype "passive"))
      (node (ref "JP.MEGA2560.DIGITAL") (pin "35") (pinfunction "35_35") (pintype "passive"))
      (node (ref "JP.MEGA2560.DIGITAL") (pin "36") (pinfunction "36_36") (pintype "passive"))
      (node (ref "JP.MEGA2560.POWER") (pin "6") (pinfunction "6_6") (pintype "passive"))
      (node (ref "JP.MEGA2560.POWER") (pin "7") (pinfunction "7_7") (pintype "passive"))
      (node (ref "JP.MISC") (pin "1") (pinfunction "1_1") (pintype "passive"))
      (node (ref "JP.MISC") (pin "2") (pinfunction "2_2") (pintype "passive"))
      (node (ref "JP.PROBE") (pin "2") (pinfunction "2_2") (pintype "passive"))
      (node (ref "JP.PWR") (pin "1") (pinfunction "1_1") (pintype "passive"))
      (node (ref "JP.SENSOR") (pin "11") (pinfunction "11_11") (pintype "passive"))
      (node (ref "JP.SENSOR") (pin "12") (pinfunction "12_12") (pintype "passive"))
      (node (ref "JP.SENSOR") (pin "17") (pinfunction "17_17") (pintype "passive"))
      (node (ref "JP.SENSOR") (pin "18") (pinfunction "18_18") (pintype "passive"))
      (node (ref "JP.SENSOR") (pin "5") (pinfunction "5_5") (pintype "passive"))
      (node (ref "JP.SENSOR") (pin "6") (pinfunction "6_6") (pintype "passive"))
      (node (ref "JP.SPINDLE") (pin "4") (pinfunction "4_4") (pintype "passive"))
      (node (ref "R12") (pin "1") (pinfunction "1_1") (pintype "passive"))
      (node (ref "R9") (pin "1") (pinfunction "1_1") (pintype "passive"))
      (node (ref "RST") (pin "1") (pinfunction "S_1") (pintype "passive"))
      (node (ref "RST") (pin "2") (pinfunction "S1_2") (pintype "passive"))
      (node (ref "U.BTN") (pin "11") (pinfunction "11_11") (pintype "passive"))
      (node (ref "U.BTN") (pin "13") (pinfunction "13_13") (pintype "passive"))
      (node (ref "U.BTN") (pin "15") (pinfunction "15_15") (pintype "passive"))
      (node (ref "U.BTN") (pin "2") (pintype "passive"))
      (node (ref "U.BTN") (pin "4") (pinfunction "4_4") (pintype "passive"))
      (node (ref "U.BTN") (pin "6") (pinfunction "6_6") (pintype "passive"))
      (node (ref "U.BTN") (pin "8") (pinfunction "8_8") (pintype "passive"))
      (node (ref "U.BTN") (pin "9") (pinfunction "9_9") (pintype "passive"))
      (node (ref "U.X.1") (pin "2") (pintype "passive"))
      (node (ref "U.X.1") (pin "3") (pintype "passive"))
      (node (ref "U.X.2") (pin "2") (pintype "passive"))
      (node (ref "U.X.2") (pin "3") (pintype "passive"))
      (node (ref "U.YZ") (pin "11") (pinfunction "11_11") (pintype "passive"))
      (node (ref "U.YZ") (pin "13") (pinfunction "13_13") (pintype "passive"))
      (node (ref "U.YZ") (pin "15") (pinfunction "15_15") (pintype "passive"))
      (node (ref "U.YZ") (pin "2") (pintype "passive"))
      (node (ref "U.YZ") (pin "4") (pinfunction "4_4") (pintype "passive"))
      (node (ref "U.YZ") (pin "6") (pinfunction "6_6") (pintype "passive"))
      (node (ref "U.YZ") (pin "8") (pinfunction "8_8") (pintype "passive"))
      (node (ref "U.YZ") (pin "9") (pinfunction "9_9") (pintype "passive"))
      (node (ref "U1") (pin "2") (pintype "passive"))
      (node (ref "U1") (pin "4") (pinfunction "4_4") (pintype "passive"))
    )
    (net (code "65") (name "Net-(D.A-A)") (class "Default")
      (node (ref "D.A") (pin "1") (pinfunction "A_1") (pintype "passive"))
      (node (ref "R.A") (pin "2") (pinfunction "2_2") (pintype "passive"))
    )
    (net (code "66") (name "Net-(D.A-K)") (class "Default")
      (node (ref "D.A") (pin "2") (pinfunction "K_2") (pintype "passive"))
      (node (ref "U.BTN") (pin "7") (pinfunction "7_7") (pintype "passive"))
    )
    (net (code "67") (name "Net-(D.D-A)") (class "Default")
      (node (ref "D.D") (pin "1") (pinfunction "A_1") (pintype "passive"))
      (node (ref "R.D") (pin "2") (pinfunction "2_2") (pintype "passive"))
    )
    (net (code "68") (name "Net-(D.D-K)") (class "Default")
      (node (ref "D.D") (pin "2") (pinfunction "K_2") (pintype "passive"))
      (node (ref "U.BTN") (pin "1") (pintype "passive"))
    )
    (net (code "69") (name "Net-(D.FLOOD-A)") (class "Default")
      (node (ref "D.FLOOD") (pin "1") (pinfunction "A_1") (pintype "passive"))
      (node (ref "R.FLOOD") (pin "2") (pinfunction "2_2") (pintype "passive"))
    )
    (net (code "70") (name "Net-(D.FLOOD-K)") (class "Default")
      (node (ref "D.FLOOD") (pin "2") (pinfunction "K_2") (pintype "passive"))
      (node (ref "U1") (pin "1") (pintype "passive"))
    )
    (net (code "71") (name "Net-(D.H-A)") (class "Default")
      (node (ref "D.H") (pin "1") (pinfunction "A_1") (pintype "passive"))
      (node (ref "R.H") (pin "2") (pinfunction "2_2") (pintype "passive"))
    )
    (net (code "72") (name "Net-(D.H-K)") (class "Default")
      (node (ref "D.H") (pin "2") (pinfunction "K_2") (pintype "passive"))
      (node (ref "U.BTN") (pin "5") (pinfunction "5_5") (pintype "passive"))
    )
    (net (code "73") (name "Net-(D.MIST-A)") (class "Default")
      (node (ref "D.MIST") (pin "1") (pinfunction "A_1") (pintype "passive"))
      (node (ref "R.MIST") (pin "2") (pinfunction "2_2") (pintype "passive"))
    )
    (net (code "74") (name "Net-(D.MIST-K)") (class "Default")
      (node (ref "D.MIST") (pin "2") (pinfunction "K_2") (pintype "passive"))
      (node (ref "U1") (pin "3") (pinfunction "3_3") (pintype "passive"))
    )
    (net (code "75") (name "Net-(D.S-A)") (class "Default")
      (node (ref "D.S") (pin "1") (pinfunction "A_1") (pintype "passive"))
      (node (ref "R.S") (pin "2") (pinfunction "2_2") (pintype "passive"))
    )
    (net (code "76") (name "Net-(D.S-K)") (class "Default")
      (node (ref "D.S") (pin "2") (pinfunction "K_2") (pintype "passive"))
      (node (ref "U.BTN") (pin "3") (pinfunction "3_3") (pintype "passive"))
    )
    (net (code "77") (name "Net-(D.X.1-A)") (class "Default")
      (node (ref "D.X.1") (pin "1") (pinfunction "A_1") (pintype "passive"))
      (node (ref "R.X.1") (pin "2") (pinfunction "2_2") (pintype "passive"))
    )
    (net (code "78") (name "Net-(D.X.1-K)") (class "Default")
      (node (ref "D.X.1") (pin "2") (pinfunction "K_2") (pintype "passive"))
      (node (ref "U.X.1") (pin "1") (pintype "passive"))
    )
    (net (code "79") (name "Net-(D.X.2-A)") (class "Default")
      (node (ref "D.X.2") (pin "1") (pinfunction "A_1") (pintype "passive"))
      (node (ref "R.X.2") (pin "2") (pinfunction "2_2") (pintype "passive"))
    )
    (net (code "80") (name "Net-(D.X.2-K)") (class "Default")
      (node (ref "D.X.2") (pin "2") (pinfunction "K_2") (pintype "passive"))
      (node (ref "U.X.2") (pin "1") (pintype "passive"))
    )
    (net (code "81") (name "Net-(D.Y.1-A)") (class "Default")
      (node (ref "D.Y.1") (pin "1") (pinfunction "A_1") (pintype "passive"))
      (node (ref "R.Y.1") (pin "2") (pinfunction "2_2") (pintype "passive"))
    )
    (net (code "82") (name "Net-(D.Y.1-K)") (class "Default")
      (node (ref "D.Y.1") (pin "2") (pinfunction "K_2") (pintype "passive"))
      (node (ref "U.YZ") (pin "5") (pinfunction "5_5") (pintype "passive"))
    )
    (net (code "83") (name "Net-(D.Y.2-A)") (class "Default")
      (node (ref "D.Y.2") (pin "1") (pinfunction "A_1") (pintype "passive"))
      (node (ref "R.Y.2") (pin "2") (pinfunction "2_2") (pintype "passive"))
    )
    (net (code "84") (name "Net-(D.Y.2-K)") (class "Default")
      (node (ref "D.Y.2") (pin "2") (pinfunction "K_2") (pintype "passive"))
      (node (ref "U.YZ") (pin "7") (pinfunction "7_7") (pintype "passive"))
    )
    (net (code "85") (name "Net-(D.Z.1-A)") (class "Default")
      (node (ref "D.Z.1") (pin "1") (pinfunction "A_1") (pintype "passive"))
      (node (ref "R.Z.1") (pin "2") (pinfunction "2_2") (pintype "passive"))
    )
    (net (code "86") (name "Net-(D.Z.1-K)") (class "Default")
      (node (ref "D.Z.1") (pin "2") (pinfunction "K_2") (pintype "passive"))
      (node (ref "U.YZ") (pin "1") (pintype "passive"))
    )
    (net (code "87") (name "Net-(D.Z.2-A)") (class "Default")
      (node (ref "D.Z.2") (pin "1") (pinfunction "A_1") (pintype "passive"))
      (node (ref "R.Z.2") (pin "2") (pinfunction "2_2") (pintype "passive"))
    )
    (net (code "88") (name "Net-(D.Z.2-K)") (class "Default")
      (node (ref "D.Z.2") (pin "2") (pinfunction "K_2") (pintype "passive"))
      (node (ref "U.YZ") (pin "3") (pinfunction "3_3") (pintype "passive"))
    )
    (net (code "89") (name "Net-(JP.BUTTONS-Pad2)") (class "Default")
      (node (ref "JP.BUTTONS") (pin "2") (pinfunction "2_2") (pintype "passive"))
      (node (ref "R.D") (pin "1") (pinfunction "1_1") (pintype "passive"))
    )
    (net (code "90") (name "Net-(JP.BUTTONS-Pad4)") (class "Default")
      (node (ref "JP.BUTTONS") (pin "4") (pinfunction "4_4") (pintype "passive"))
      (node (ref "R.S") (pin "1") (pinfunction "1_1") (pintype "passive"))
    )
    (net (code "91") (name "Net-(JP.BUTTONS-Pad6)") (class "Default")
      (node (ref "JP.BUTTONS") (pin "6") (pinfunction "6_6") (pintype "passive"))
      (node (ref "R.H") (pin "1") (pinfunction "1_1") (pintype "passive"))
    )
    (net (code "92") (name "Net-(JP.BUTTONS-Pad8)") (class "Default")
      (node (ref "JP.BUTTONS") (pin "8") (pinfunction "8_8") (pintype "passive"))
      (node (ref "R.A") (pin "1") (pinfunction "1_1") (pintype "passive"))
    )
    (net (code "93") (name "Net-(JP.COOLANT-Pad1)") (class "Default")
      (node (ref "JP.COOLANT") (pin "1") (pinfunction "1_1") (pintype "passive"))
      (node (ref "U1") (pin "5") (pinfunction "5_5") (pintype "passive"))
    )
    (net (code "94") (name "Net-(JP.COOLANT-Pad2)") (class "Default")
      (node (ref "JP.COOLANT") (pin "2") (pinfunction "2_2") (pintype "passive"))
      (node (ref "U1") (pin "6") (pinfunction "6_6") (pintype "passive"))
    )
    (net (code "95") (name "Net-(JP.COOLANT-Pad3)") (class "Default")
      (node (ref "JP.COOLANT") (pin "3") (pinfunction "3_3") (pintype "passive"))
      (node (ref "U1") (pin "7") (pinfunction "7_7") (pintype "passive"))
    )
    (net (code "96") (name "Net-(JP.COOLANT-Pad4)") (class "Default")
      (node (ref "JP.COOLANT") (pin "4") (pinfunction "4_4") (pintype "passive"))
      (node (ref "U1") (pin "8") (pinfunction "8_8") (pintype "passive"))
    )
    (net (code "97") (name "unconnected-(JP.MEGA2560.ANALOG.HIGH-Pad5)") (class "Default")
      (node (ref "JP.MEGA2560.ANALOG.HIGH") (pin "5") (pinfunction "5_5") (pintype "passive"))
    )
    (net (code "98") (name "unconnected-(JP.MEGA2560.ANALOG.HIGH-Pad6)") (class "Default")
      (node (ref "JP.MEGA2560.ANALOG.HIGH") (pin "6") (pinfunction "6_6") (pintype "passive"))
    )
    (net (code "99") (name "unconnected-(JP.MEGA2560.ANALOG.HIGH-Pad7)") (class "Default")
      (node (ref "JP.MEGA2560.ANALOG.HIGH") (pin "7") (pinfunction "7_7") (pintype "passive"))
    )
    (net (code "100") (name "unconnected-(JP.MEGA2560.ANALOG.LOW-Pad1)") (class "Default")
      (node (ref "JP.MEGA2560.ANALOG.LOW") (pin "1") (pinfunction "1_1") (pintype "passive"))
    )
    (net (code "101") (name "unconnected-(JP.MEGA2560.ANALOG.LOW-Pad2)") (class "Default")
      (node (ref "JP.MEGA2560.ANALOG.LOW") (pin "2") (pinfunction "2_2") (pintype "passive"))
    )
    (net (code "102") (name "unconnected-(JP.MEGA2560.ANALOG.LOW-Pad3)") (class "Default")
      (node (ref "JP.MEGA2560.ANALOG.LOW") (pin "3") (pinfunction "3_3") (pintype "passive"))
    )
    (net (code "103") (name "unconnected-(JP.MEGA2560.ANALOG.LOW-Pad4)") (class "Default")
      (node (ref "JP.MEGA2560.ANALOG.LOW") (pin "4") (pinfunction "4_4") (pintype "passive"))
    )
    (net (code "104") (name "unconnected-(JP.MEGA2560.ANALOG.LOW-Pad5)") (class "Default")
      (node (ref "JP.MEGA2560.ANALOG.LOW") (pin "5") (pinfunction "5_5") (pintype "passive"))
    )
    (net (code "105") (name "unconnected-(JP.MEGA2560.ANALOG.LOW-Pad6)") (class "Default")
      (node (ref "JP.MEGA2560.ANALOG.LOW") (pin "6") (pinfunction "6_6") (pintype "passive"))
    )
    (net (code "106") (name "unconnected-(JP.MEGA2560.ANALOG.LOW-Pad7)") (class "Default")
      (node (ref "JP.MEGA2560.ANALOG.LOW") (pin "7") (pinfunction "7_7") (pintype "passive"))
    )
    (net (code "107") (name "unconnected-(JP.MEGA2560.ANALOG.LOW-Pad8)") (class "Default")
      (node (ref "JP.MEGA2560.ANALOG.LOW") (pin "8") (pinfunction "8_8") (pintype "passive"))
    )
    (net (code "108") (name "unconnected-(JP.MEGA2560.DIGITAL-Pad1)") (class "Default")
      (node (ref "JP.MEGA2560.DIGITAL") (pin "1") (pinfunction "1_1") (pintype "passive"))
    )
    (net (code "109") (name "unconnected-(JP.MEGA2560.DIGITAL-Pad2)") (class "Default")
      (node (ref "JP.MEGA2560.DIGITAL") (pin "2") (pinfunction "2_2") (pintype "passive"))
    )
    (net (code "110") (name "unconnected-(JP.MEGA2560.DIGITAL-Pad3)") (class "Default")
      (node (ref "JP.MEGA2560.DIGITAL") (pin "3") (pinfunction "3_3") (pintype "passive"))
    )
    (net (code "111") (name "unconnected-(JP.MEGA2560.DIGITAL-Pad4)") (class "Default")
      (node (ref "JP.MEGA2560.DIGITAL") (pin "4") (pinfunction "4_4") (pintype "passive"))
    )
    (net (code "112") (name "unconnected-(JP.MEGA2560.DIGITAL-Pad8)") (class "Default")
      (node (ref "JP.MEGA2560.DIGITAL") (pin "8") (pinfunction "8_8") (pintype "passive"))
    )
    (net (code "113") (name "unconnected-(JP.MEGA2560.DIGITAL-Pad9)") (class "Default")
      (node (ref "JP.MEGA2560.DIGITAL") (pin "9") (pinfunction "9_9") (pintype "passive"))
    )
    (net (code "114") (name "unconnected-(JP.MEGA2560.DIGITAL-Pad10)") (class "Default")
      (node (ref "JP.MEGA2560.DIGITAL") (pin "10") (pinfunction "10_10") (pintype "passive"))
    )
    (net (code "115") (name "unconnected-(JP.MEGA2560.DIGITAL-Pad14)") (class "Default")
      (node (ref "JP.MEGA2560.DIGITAL") (pin "14") (pinfunction "14_14") (pintype "passive"))
    )
    (net (code "116") (name "unconnected-(JP.MEGA2560.POWER-Pad1)") (class "Default")
      (node (ref "JP.MEGA2560.POWER") (pin "1") (pinfunction "1_1") (pintype "passive"))
    )
    (net (code "117") (name "unconnected-(JP.MEGA2560.POWER-Pad2)") (class "Default")
      (node (ref "JP.MEGA2560.POWER") (pin "2") (pinfunction "2_2") (pintype "passive"))
    )
    (net (code "118") (name "unconnected-(JP.MEGA2560.POWER-Pad4)") (class "Default")
      (node (ref "JP.MEGA2560.POWER") (pin "4") (pinfunction "4_4") (pintype "passive"))
    )
    (net (code "119") (name "unconnected-(JP.MEGA2560.POWER-Pad5)") (class "Default")
      (node (ref "JP.MEGA2560.POWER") (pin "5") (pinfunction "5_5") (pintype "passive"))
    )
    (net (code "120") (name "unconnected-(JP.MEGA2560.PWM.HIGH-Pad1)") (class "Default")
      (node (ref "JP.MEGA2560.PWM.HIGH") (pin "1") (pinfunction "1_1") (pintype "passive"))
    )
    (net (code "121") (name "unconnected-(JP.MEGA2560.PWM.HIGH-Pad2)") (class "Default")
      (node (ref "JP.MEGA2560.PWM.HIGH") (pin "2") (pinfunction "2_2") (pintype "passive"))
    )
    (net (code "122") (name "unconnected-(JP.MEGA2560.PWM.HIGH-Pad3)") (class "Default")
      (node (ref "JP.MEGA2560.PWM.HIGH") (pin "3") (pinfunction "3_3") (pintype "passive"))
    )
    (net (code "123") (name "unconnected-(JP.MEGA2560.PWM.HIGH-Pad4)") (class "Default")
      (node (ref "JP.MEGA2560.PWM.HIGH") (pin "4") (pinfunction "4_4") (pintype "passive"))
    )
    (net (code "124") (name "unconnected-(JP.MEGA2560.PWM.LOW-Pad4)") (class "Default")
      (node (ref "JP.MEGA2560.PWM.LOW") (pin "4") (pinfunction "4_4") (pintype "passive"))
    )
    (net (code "125") (name "unconnected-(JP.MEGA2560.PWM.LOW-Pad5)") (class "Default")
      (node (ref "JP.MEGA2560.PWM.LOW") (pin "5") (pinfunction "5_5") (pintype "passive"))
    )
    (net (code "126") (name "unconnected-(JP.MEGA2560.PWM.LOW-Pad6)") (class "Default")
      (node (ref "JP.MEGA2560.PWM.LOW") (pin "6") (pinfunction "6_6") (pintype "passive"))
    )
  )
)
